# Sheet1.net
KiCad netlist of a schematic drawn in Altium Designer
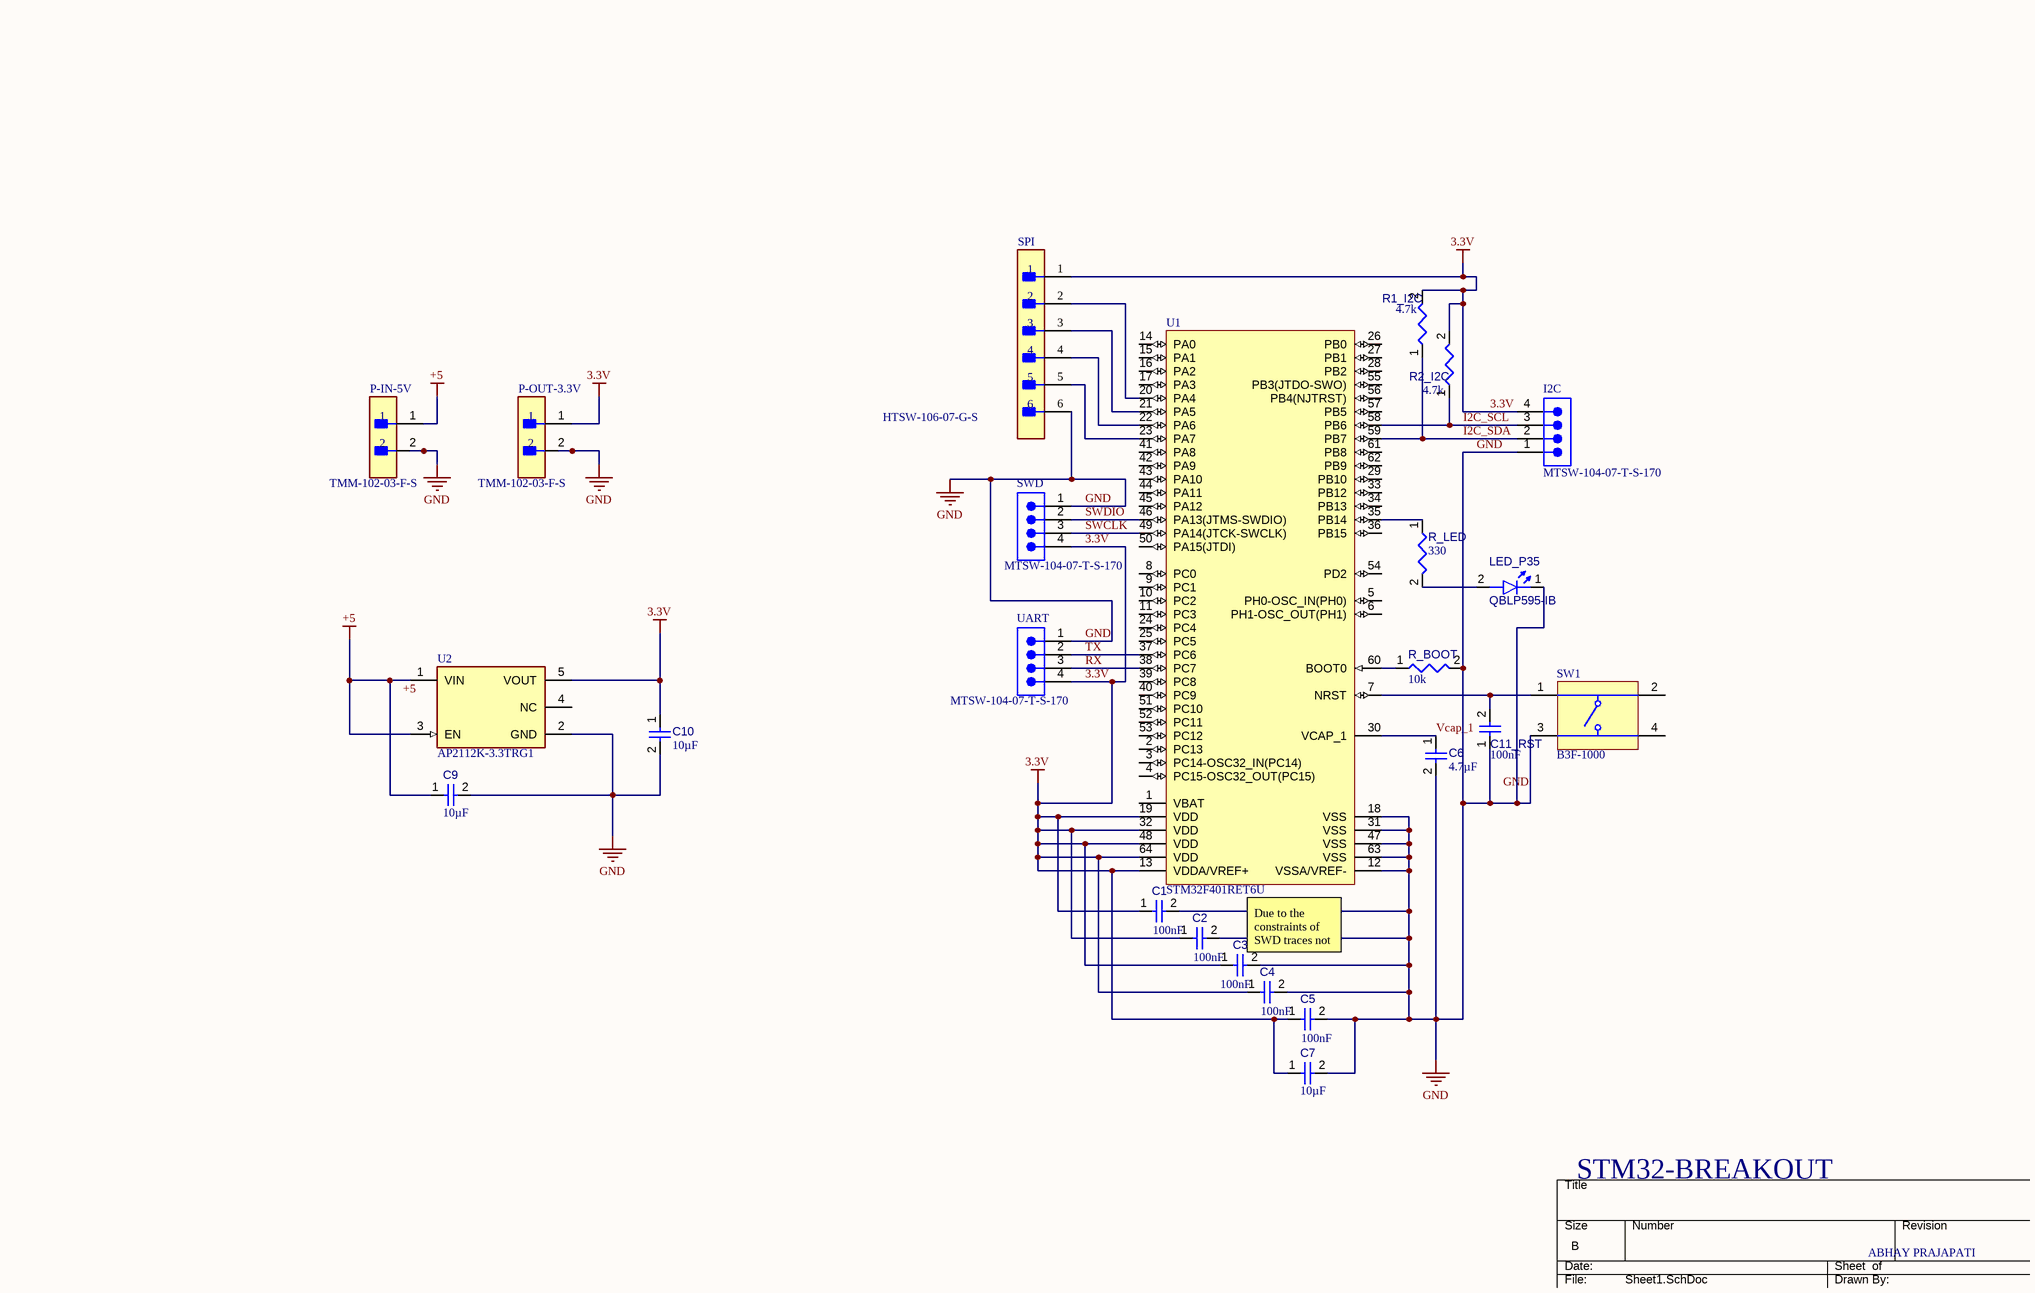
[diagram p0: Sheet1.SchDoc]

(export (version "E")
  (design (tool "Eeschema 10.0.6"))
  (components
    (comp (ref "C1")
      (value "100nF")
      (footprint "CAPC0402(1005)60_L")
      (description "Chip Capacitor, 100nF +/-20%, 25V, 0402, Thickness 0.6 mm")
      (fields (field (name "TOLERANCE") "10%") (field (name "Comment") "Capacitor 100nF +/-20% 25V 0402"))
      (libsource (lib "Abhay Prajapati") (part "CAP-NP-2"))
    )
    (comp (ref "C2")
      (value "100nF")
      (footprint "CAPC0402(1005)60_L")
      (description "Chip Capacitor, 100nF +/-20%, 25V, 0402, Thickness 0.6 mm")
      (fields (field (name "TOLERANCE") "10%") (field (name "Comment") "Capacitor 100nF +/-20% 25V 0402"))
      (libsource (lib "Abhay Prajapati") (part "CAP-NP-2"))
    )
    (comp (ref "C3_NOT")
      (value "100nF")
      (footprint "CAPC0402(1005)60_L")
      (description "Chip Capacitor, 100nF +/-20%, 25V, 0402, Thickness 0.6 mm")
      (fields (field (name "TOLERANCE") "10%") (field (name "Comment") "Capacitor 100nF +/-20% 25V 0402"))
      (libsource (lib "Abhay Prajapati") (part "CAP-NP-2"))
    )
    (comp (ref "C4")
      (value "100nF")
      (footprint "CAPC0402(1005)60_L")
      (description "Chip Capacitor, 100nF +/-20%, 25V, 0402, Thickness 0.6 mm")
      (fields (field (name "TOLERANCE") "10%") (field (name "Comment") "Capacitor 100nF +/-20% 25V 0402"))
      (libsource (lib "Abhay Prajapati") (part "CAP-NP-2"))
    )
    (comp (ref "C5")
      (value "100nF")
      (footprint "CAPC0402(1005)60_L")
      (description "Chip Capacitor, 100nF +/-20%, 25V, 0402, Thickness 0.6 mm")
      (fields (field (name "TOLERANCE") "10%") (field (name "Comment") "Capacitor 100nF +/-20% 25V 0402"))
      (libsource (lib "Abhay Prajapati") (part "CAP-NP-2"))
    )
    (comp (ref "C6")
      (value "4.7µF")
      (footprint "CAPC0603(1608)100_L")
      (description "Chip Capacitor, 4.7µF +/-20%, 10V, 0603, Thickness 1 mm")
      (fields (field (name "TOLERANCE") "10%") (field (name "Comment") "Capacitor 4.7µF +/-20% 10V 0603"))
      (libsource (lib "Abhay Prajapati") (part "CAP-NP-2"))
    )
    (comp (ref "C7")
      (value "10µF")
      (footprint "FP-GRM21B-0_1-IPC_B")
      (description "16V 10uF X5R ±10% 0805 Multilayer Ceramic Capacitors MLCC - SMD/SMT ROHS")
      (fields (field (name "TOLERANCE") "10%") (field (name "Comment") "GRM21BR61C106KE15K"))
      (libsource (lib "Abhay Prajapati") (part "CAP-NP-2"))
    )
    (comp (ref "C9")
      (value "10µF")
      (footprint "CAPC2013X135X45NL10T25")
      (description "Chip Capacitor, 10 uF, +/- 10%, 16 V, 0805 (2012 Metric)")
      (fields (field (name "TOLERANCE") "10%") (field (name "Comment") "Capacitor 10 uF +/- 10% 16 V 0805"))
      (libsource (lib "Abhay Prajapati") (part "CAP-NP-2"))
    )
    (comp (ref "C10")
      (value "10µF")
      (footprint "CAPC2013X135X45NL10T25")
      (description "Chip Capacitor, 10 uF, +/- 10%, 16 V, 0805 (2012 Metric)")
      (fields (field (name "TOLERANCE") "10%") (field (name "Comment") "Capacitor 10 uF +/- 10% 16 V 0805"))
      (libsource (lib "Abhay Prajapati") (part "CAP-NP-2"))
    )
    (comp (ref "C11_RST")
      (value "100nF")
      (footprint "CAPC1608X90X40NL10T20")
      (description "Chip Capacitor, 100 nF, +/- 10%, 50 V, 0603 (1608 Metric)")
      (fields (field (name "TOLERANCE") "10%") (field (name "Comment") "Capacitor 100 nF +/-10% 50 V 0603"))
      (libsource (lib "Abhay Prajapati") (part "CAP-NP-2"))
    )
    (comp (ref "I2C")
      (value "MTSW-104-07-T-S-170")
      (footprint "SMTC-MTSW-104-07-X-S-170")
      (description "Headers & Wire Housings Variable Height PCB Header Strips, 0.100 pitch")
      (libsource (lib "Abhay Prajapati") (part "SMTC-MTSW-104-07-X-S-170"))
    )
    (comp (ref "LED_P35")
      (value "QBLP595-IB")
      (footprint "QTB-QBLP595_V")
      (description "Chip LED 0402, Blue, 0.02 A, 3.1 to 3.7 V, -40 to 80 degC, 2-Pin SMD, RoHS, Tape and Reel")
      (libsource (lib "Abhay Prajapati") (part "LED-KA-2"))
    )
    (comp (ref "P-IN-5V")
      (value "TMM-102-03-F-S")
      (footprint "FP-TMM-102-03-F-S-MFG")
      (description "Pin Header, Board-to-Board, Wire-to-Board, 2 mm, 1 Rows, 2 Contacts, Through Hole, TMM")
      (libsource (lib "Abhay Prajapati") (part "3bc925449376181038e59eaffc5286c"))
    )
    (comp (ref "P-OUT-3.3V")
      (value "TMM-102-03-F-S")
      (footprint "FP-TMM-102-03-F-S-MFG")
      (description "Pin Header, Board-to-Board, Wire-to-Board, 2 mm, 1 Rows, 2 Contacts, Through Hole, TMM")
      (libsource (lib "Abhay Prajapati") (part "3bc925449376181038e59eaffc5286c"))
    )
    (comp (ref "R1_I2C")
      (value "4.7k")
      (footprint "RESC0402(1005)_L")
      (description "4K7 0.063W 1% 0402 (1005 Metric)  SMD")
      (fields (field (name "TOLERANCE") "1%") (field (name "POWER") "63mW"))
      (libsource (lib "Abhay Prajapati") (part "4D7KR2F"))
    )
    (comp (ref "R2_I2C")
      (value "4.7k")
      (footprint "RESC0402(1005)_L")
      (description "4K7 0.063W 1% 0402 (1005 Metric)  SMD")
      (fields (field (name "TOLERANCE") "1%") (field (name "POWER") "63mW"))
      (libsource (lib "Abhay Prajapati") (part "4D7KR2F"))
    )
    (comp (ref "R_BOOT")
      (value "10k")
      (footprint "RESC3216X60X45ML15T20")
      (description "Chip Resistor, 10 KOhm, +/- 1%, 0.25 W, -55 to 155 degC, 1206 (3216 Metric)")
      (fields (field (name "TOLERANCE") "1%") (field (name "POWER") "250mW"))
      (libsource (lib "Abhay Prajapati") (part "RES-2"))
    )
    (comp (ref "R_LED")
      (value "330")
      (footprint "RESC0402(1005)_L")
      (description "330R 0.063W 5% 0402 (1005 Metric)  SMD")
      (fields (field (name "TOLERANCE") "5%") (field (name "POWER") "63mW"))
      (libsource (lib "Abhay Prajapati") (part "330R2J"))
    )
    (comp (ref "SPI")
      (value "HTSW-106-07-G-S")
      (footprint "FP-HTSW-106-07-G-S-MFG")
      (description "Pin Header, Vertical, Board-to-Board, 2.54 mm, 1 Rows, 6 Contacts, Through Hole, HTSW Series")
      (libsource (lib "Abhay Prajapati") (part "f2cb566baf1c37ab5a3b8e90bbeafd6"))
    )
    (comp (ref "SW1")
      (value "B3F-1000")
      (footprint "OMRON-B3F-1000-4_V")
      (description "Tactile Switch, SPST-NO, 0.05 A, 24 V, -25 to 70 degC, 4-Pin THD, RoHS, Bulk")
      (fields (field (name "MANUFACTURER") "Omron Electronic Components"))
      (libsource (lib "Abhay Prajapati") (part "SW-SPST-4_A"))
    )
    (comp (ref "SWD")
      (value "MTSW-104-07-T-S-170")
      (footprint "SMTC-MTSW-104-07-X-S-170")
      (description "Headers & Wire Housings Variable Height PCB Header Strips, 0.100 pitch")
      (libsource (lib "Abhay Prajapati") (part "SMTC-MTSW-104-07-X-S-170"))
    )
    (comp (ref "U1")
      (value "STM32F401RET6U")
      (footprint "STM-LQFP64_L")
      (description "MCU 32-Bit STM32 ARM Cortex M4 RISC 512KB Flash 2.5V/3.3V 64-Pin LQFP Tray")
      (libsource (lib "Abhay Prajapati") (part "MC-ARM-STM32F401-LQFP64"))
    )
    (comp (ref "U2")
      (value "AP2112K-3.3TRG1")
      (footprint "FP-SOT25-IPC_B")
      (description "AP2112 Series 0.6 A 3.3 V Fixed Output SMT LDO Linear Regulator - SOT23-5")
      (libsource (lib "Abhay Prajapati") (part "c8ab751aee5229183125ab046a11caa"))
    )
    (comp (ref "UART")
      (value "MTSW-104-07-T-S-170")
      (footprint "SMTC-MTSW-104-07-X-S-170")
      (description "Headers & Wire Housings Variable Height PCB Header Strips, 0.100 pitch")
      (libsource (lib "Abhay Prajapati") (part "SMTC-MTSW-104-07-X-S-170"))
    )
  )
  (nets
    (net (code "1") (name "+5") (class "Default")
      (node (ref "C9") (pin "1") (pinfunction "1_1") (pintype "passive"))
      (node (ref "P-IN-5V") (pin "1") (pinfunction "1_1") (pintype "passive"))
      (node (ref "U2") (pin "1") (pinfunction "VIN_1") (pintype "power_in"))
      (node (ref "U2") (pin "3") (pinfunction "EN_3") (pintype "input"))
    )
    (net (code "2") (name "/I2C_SCL") (class "Default")
      (node (ref "I2C") (pin "3") (pinfunction "3_3") (pintype "passive"))
      (node (ref "R2_I2C") (pin "1") (pinfunction "1_1") (pintype "passive"))
      (node (ref "U1") (pin "58") (pinfunction "PB6_58") (pintype "bidirectional"))
    )
    (net (code "3") (name "/I2C_SDA") (class "Default")
      (node (ref "I2C") (pin "2") (pinfunction "2_2") (pintype "passive"))
      (node (ref "R1_I2C") (pin "1") (pinfunction "1_1") (pintype "passive"))
      (node (ref "U1") (pin "59") (pinfunction "PB7_59") (pintype "bidirectional"))
    )
    (net (code "4") (name "/RX") (class "Default")
      (node (ref "U1") (pin "38") (pinfunction "PC7_38") (pintype "bidirectional"))
      (node (ref "UART") (pin "3") (pinfunction "3_3") (pintype "passive"))
    )
    (net (code "5") (name "/SWCLK") (class "Default")
      (node (ref "SWD") (pin "3") (pinfunction "3_3") (pintype "passive"))
      (node (ref "U1") (pin "49") (pinfunction "PA14(JTCK-SWCLK)_49") (pintype "bidirectional"))
    )
    (net (code "6") (name "/SWDIO") (class "Default")
      (node (ref "SWD") (pin "2") (pinfunction "2_2") (pintype "passive"))
      (node (ref "U1") (pin "46") (pinfunction "PA13(JTMS-SWDIO)_46") (pintype "bidirectional"))
    )
    (net (code "7") (name "/TX") (class "Default")
      (node (ref "U1") (pin "37") (pinfunction "PC6_37") (pintype "bidirectional"))
      (node (ref "UART") (pin "2") (pinfunction "2_2") (pintype "passive"))
    )
    (net (code "8") (name "/Vcap_1") (class "Default")
      (node (ref "C6") (pin "1") (pinfunction "1_1") (pintype "passive"))
      (node (ref "U1") (pin "30") (pinfunction "VCAP_1_30") (pintype "passive"))
    )
    (net (code "9") (name "3.3V") (class "Default")
      (node (ref "C1") (pin "1") (pinfunction "1_1") (pintype "passive"))
      (node (ref "C10") (pin "1") (pinfunction "1_1") (pintype "passive"))
      (node (ref "C2") (pin "1") (pinfunction "1_1") (pintype "passive"))
      (node (ref "C3_NOT") (pin "1") (pinfunction "1_1") (pintype "passive"))
      (node (ref "C4") (pin "1") (pinfunction "1_1") (pintype "passive"))
      (node (ref "C5") (pin "1") (pinfunction "1_1") (pintype "passive"))
      (node (ref "C7") (pin "1") (pinfunction "1_1") (pintype "passive"))
      (node (ref "I2C") (pin "4") (pinfunction "4_4") (pintype "passive"))
      (node (ref "P-OUT-3.3V") (pin "1") (pinfunction "1_1") (pintype "passive"))
      (node (ref "R1_I2C") (pin "2") (pinfunction "2_2") (pintype "passive"))
      (node (ref "R2_I2C") (pin "2") (pinfunction "2_2") (pintype "passive"))
      (node (ref "SPI") (pin "1") (pinfunction "1_1") (pintype "passive"))
      (node (ref "SWD") (pin "4") (pinfunction "4_4") (pintype "passive"))
      (node (ref "U1") (pin "13") (pinfunction "VDDA/VREF+_13") (pintype "power_in"))
      (node (ref "U1") (pin "19") (pinfunction "VDD_19") (pintype "power_in"))
      (node (ref "U1") (pin "32") (pinfunction "VDD_32") (pintype "power_in"))
      (node (ref "U1") (pin "48") (pinfunction "VDD_48") (pintype "power_in"))
      (node (ref "U1") (pin "64") (pinfunction "VDD_64") (pintype "power_in"))
      (node (ref "U2") (pin "5") (pinfunction "VOUT_5") (pintype "power_in"))
      (node (ref "UART") (pin "4") (pinfunction "4_4") (pintype "passive"))
    )
    (net (code "10") (name "GND") (class "Default")
      (node (ref "C1") (pin "2") (pinfunction "2_2") (pintype "passive"))
      (node (ref "C10") (pin "2") (pinfunction "2_2") (pintype "passive"))
      (node (ref "C11_RST") (pin "1") (pinfunction "1_1") (pintype "passive"))
      (node (ref "C2") (pin "2") (pinfunction "2_2") (pintype "passive"))
      (node (ref "C3_NOT") (pin "2") (pinfunction "2_2") (pintype "passive"))
      (node (ref "C4") (pin "2") (pinfunction "2_2") (pintype "passive"))
      (node (ref "C5") (pin "2") (pinfunction "2_2") (pintype "passive"))
      (node (ref "C6") (pin "2") (pinfunction "2_2") (pintype "passive"))
      (node (ref "C7") (pin "2") (pinfunction "2_2") (pintype "passive"))
      (node (ref "C9") (pin "2") (pinfunction "2_2") (pintype "passive"))
      (node (ref "I2C") (pin "1") (pinfunction "1_1") (pintype "passive"))
      (node (ref "LED_P35") (pin "1") (pinfunction "K_1") (pintype "passive"))
      (node (ref "P-IN-5V") (pin "2") (pinfunction "2_2") (pintype "passive"))
      (node (ref "P-OUT-3.3V") (pin "2") (pinfunction "2_2") (pintype "passive"))
      (node (ref "R_BOOT") (pin "2") (pinfunction "2_2") (pintype "passive"))
      (node (ref "SPI") (pin "6") (pinfunction "6_6") (pintype "passive"))
      (node (ref "SW1") (pin "3") (pinfunction "3_3") (pintype "passive"))
      (node (ref "SWD") (pin "1") (pinfunction "1_1") (pintype "passive"))
      (node (ref "U1") (pin "12") (pinfunction "VSSA/VREF-_12") (pintype "power_in"))
      (node (ref "U1") (pin "18") (pinfunction "VSS_18") (pintype "power_in"))
      (node (ref "U1") (pin "31") (pinfunction "VSS_31") (pintype "power_in"))
      (node (ref "U1") (pin "47") (pinfunction "VSS_47") (pintype "power_in"))
      (node (ref "U1") (pin "63") (pinfunction "VSS_63") (pintype "power_in"))
      (node (ref "U2") (pin "2") (pinfunction "GND_2") (pintype "power_in"))
      (node (ref "UART") (pin "1") (pinfunction "1_1") (pintype "passive"))
    )
    (net (code "11") (name "Net-(LED_P35-A)") (class "Default")
      (node (ref "LED_P35") (pin "2") (pinfunction "A_2") (pintype "passive"))
      (node (ref "R_LED") (pin "2") (pinfunction "2_2") (pintype "passive"))
    )
    (net (code "12") (name "Net-(U1-BOOT0)") (class "Default")
      (node (ref "R_BOOT") (pin "1") (pinfunction "1_1") (pintype "passive"))
      (node (ref "U1") (pin "60") (pinfunction "BOOT0_60") (pintype "input"))
    )
    (net (code "13") (name "Net-(U1-NRST)") (class "Default")
      (node (ref "C11_RST") (pin "2") (pinfunction "2_2") (pintype "passive"))
      (node (ref "SW1") (pin "1") (pinfunction "1_1") (pintype "passive"))
      (node (ref "U1") (pin "7") (pinfunction "NRST_7") (pintype "bidirectional"))
    )
    (net (code "14") (name "Net-(U1-PA4)") (class "Default")
      (node (ref "SPI") (pin "2") (pinfunction "2_2") (pintype "passive"))
      (node (ref "U1") (pin "20") (pinfunction "PA4_20") (pintype "bidirectional"))
    )
    (net (code "15") (name "Net-(U1-PA5)") (class "Default")
      (node (ref "SPI") (pin "3") (pinfunction "3_3") (pintype "passive"))
      (node (ref "U1") (pin "21") (pinfunction "PA5_21") (pintype "bidirectional"))
    )
    (net (code "16") (name "Net-(U1-PA6)") (class "Default")
      (node (ref "SPI") (pin "4") (pinfunction "4_4") (pintype "passive"))
      (node (ref "U1") (pin "22") (pinfunction "PA6_22") (pintype "bidirectional"))
    )
    (net (code "17") (name "Net-(U1-PA7)") (class "Default")
      (node (ref "SPI") (pin "5") (pinfunction "5_5") (pintype "passive"))
      (node (ref "U1") (pin "23") (pinfunction "PA7_23") (pintype "bidirectional"))
    )
    (net (code "18") (name "Net-(U1-PB14)") (class "Default")
      (node (ref "R_LED") (pin "1") (pinfunction "1_1") (pintype "passive"))
      (node (ref "U1") (pin "35") (pinfunction "PB14_35") (pintype "bidirectional"))
    )
    (net (code "19") (name "unconnected-(SW1-Pad2)") (class "Default")
      (node (ref "SW1") (pin "2") (pinfunction "2_2") (pintype "passive"))
    )
    (net (code "20") (name "unconnected-(SW1-Pad4)") (class "Default")
      (node (ref "SW1") (pin "4") (pinfunction "4_4") (pintype "passive"))
    )
    (net (code "21") (name "unconnected-(U1-PA0-Pad14)") (class "Default")
      (node (ref "U1") (pin "14") (pinfunction "PA0_14") (pintype "bidirectional"))
    )
    (net (code "22") (name "unconnected-(U1-PA1-Pad15)") (class "Default")
      (node (ref "U1") (pin "15") (pinfunction "PA1_15") (pintype "bidirectional"))
    )
    (net (code "23") (name "unconnected-(U1-PA2-Pad16)") (class "Default")
      (node (ref "U1") (pin "16") (pinfunction "PA2_16") (pintype "bidirectional"))
    )
    (net (code "24") (name "unconnected-(U1-PA3-Pad17)") (class "Default")
      (node (ref "U1") (pin "17") (pinfunction "PA3_17") (pintype "bidirectional"))
    )
    (net (code "25") (name "unconnected-(U1-PA8-Pad41)") (class "Default")
      (node (ref "U1") (pin "41") (pinfunction "PA8_41") (pintype "bidirectional"))
    )
    (net (code "26") (name "unconnected-(U1-PA9-Pad42)") (class "Default")
      (node (ref "U1") (pin "42") (pinfunction "PA9_42") (pintype "bidirectional"))
    )
    (net (code "27") (name "unconnected-(U1-PA10-Pad43)") (class "Default")
      (node (ref "U1") (pin "43") (pinfunction "PA10_43") (pintype "bidirectional"))
    )
    (net (code "28") (name "unconnected-(U1-PA11-Pad44)") (class "Default")
      (node (ref "U1") (pin "44") (pinfunction "PA11_44") (pintype "bidirectional"))
    )
    (net (code "29") (name "unconnected-(U1-PA12-Pad45)") (class "Default")
      (node (ref "U1") (pin "45") (pinfunction "PA12_45") (pintype "bidirectional"))
    )
    (net (code "30") (name "unconnected-(U1-PA15(JTDI)-Pad50)") (class "Default")
      (node (ref "U1") (pin "50") (pinfunction "PA15(JTDI)_50") (pintype "bidirectional"))
    )
    (net (code "31") (name "unconnected-(U1-PB0-Pad26)") (class "Default")
      (node (ref "U1") (pin "26") (pinfunction "PB0_26") (pintype "bidirectional"))
    )
    (net (code "32") (name "unconnected-(U1-PB1-Pad27)") (class "Default")
      (node (ref "U1") (pin "27") (pinfunction "PB1_27") (pintype "bidirectional"))
    )
    (net (code "33") (name "unconnected-(U1-PB2-Pad28)") (class "Default")
      (node (ref "U1") (pin "28") (pinfunction "PB2_28") (pintype "bidirectional"))
    )
    (net (code "34") (name "unconnected-(U1-PB3(JTDO-SWO)-Pad55)") (class "Default")
      (node (ref "U1") (pin "55") (pinfunction "PB3(JTDO-SWO)_55") (pintype "bidirectional"))
    )
    (net (code "35") (name "unconnected-(U1-PB4(NJTRST)-Pad56)") (class "Default")
      (node (ref "U1") (pin "56") (pinfunction "PB4(NJTRST)_56") (pintype "bidirectional"))
    )
    (net (code "36") (name "unconnected-(U1-PB5-Pad57)") (class "Default")
      (node (ref "U1") (pin "57") (pinfunction "PB5_57") (pintype "bidirectional"))
    )
    (net (code "37") (name "unconnected-(U1-PB8-Pad61)") (class "Default")
      (node (ref "U1") (pin "61") (pinfunction "PB8_61") (pintype "bidirectional"))
    )
    (net (code "38") (name "unconnected-(U1-PB9-Pad62)") (class "Default")
      (node (ref "U1") (pin "62") (pinfunction "PB9_62") (pintype "bidirectional"))
    )
    (net (code "39") (name "unconnected-(U1-PB10-Pad29)") (class "Default")
      (node (ref "U1") (pin "29") (pinfunction "PB10_29") (pintype "bidirectional"))
    )
    (net (code "40") (name "unconnected-(U1-PB12-Pad33)") (class "Default")
      (node (ref "U1") (pin "33") (pinfunction "PB12_33") (pintype "bidirectional"))
    )
    (net (code "41") (name "unconnected-(U1-PB13-Pad34)") (class "Default")
      (node (ref "U1") (pin "34") (pinfunction "PB13_34") (pintype "bidirectional"))
    )
    (net (code "42") (name "unconnected-(U1-PB15-Pad36)") (class "Default")
      (node (ref "U1") (pin "36") (pinfunction "PB15_36") (pintype "bidirectional"))
    )
    (net (code "43") (name "unconnected-(U1-PC0-Pad8)") (class "Default")
      (node (ref "U1") (pin "8") (pinfunction "PC0_8") (pintype "bidirectional"))
    )
    (net (code "44") (name "unconnected-(U1-PC1-Pad9)") (class "Default")
      (node (ref "U1") (pin "9") (pinfunction "PC1_9") (pintype "bidirectional"))
    )
    (net (code "45") (name "unconnected-(U1-PC2-Pad10)") (class "Default")
      (node (ref "U1") (pin "10") (pinfunction "PC2_10") (pintype "bidirectional"))
    )
    (net (code "46") (name "unconnected-(U1-PC3-Pad11)") (class "Default")
      (node (ref "U1") (pin "11") (pinfunction "PC3_11") (pintype "bidirectional"))
    )
    (net (code "47") (name "unconnected-(U1-PC4-Pad24)") (class "Default")
      (node (ref "U1") (pin "24") (pinfunction "PC4_24") (pintype "bidirectional"))
    )
    (net (code "48") (name "unconnected-(U1-PC5-Pad25)") (class "Default")
      (node (ref "U1") (pin "25") (pinfunction "PC5_25") (pintype "bidirectional"))
    )
    (net (code "49") (name "unconnected-(U1-PC8-Pad39)") (class "Default")
      (node (ref "U1") (pin "39") (pinfunction "PC8_39") (pintype "bidirectional"))
    )
    (net (code "50") (name "unconnected-(U1-PC9-Pad40)") (class "Default")
      (node (ref "U1") (pin "40") (pinfunction "PC9_40") (pintype "bidirectional"))
    )
    (net (code "51") (name "unconnected-(U1-PC10-Pad51)") (class "Default")
      (node (ref "U1") (pin "51") (pinfunction "PC10_51") (pintype "bidirectional"))
    )
    (net (code "52") (name "unconnected-(U1-PC11-Pad52)") (class "Default")
      (node (ref "U1") (pin "52") (pinfunction "PC11_52") (pintype "bidirectional"))
    )
    (net (code "53") (name "unconnected-(U1-PC12-Pad53)") (class "Default")
      (node (ref "U1") (pin "53") (pinfunction "PC12_53") (pintype "bidirectional"))
    )
    (net (code "54") (name "unconnected-(U1-PC13-Pad2)") (class "Default")
      (node (ref "U1") (pin "2") (pinfunction "PC13_2") (pintype "bidirectional"))
    )
    (net (code "55") (name "unconnected-(U1-PC14-OSC32_IN(PC14)-Pad3)") (class "Default")
      (node (ref "U1") (pin "3") (pinfunction "PC14-OSC32_IN(PC14)_3") (pintype "bidirectional"))
    )
    (net (code "56") (name "unconnected-(U1-PC15-OSC32_OUT(PC15)-Pad4)") (class "Default")
      (node (ref "U1") (pin "4") (pinfunction "PC15-OSC32_OUT(PC15)_4") (pintype "bidirectional"))
    )
    (net (code "57") (name "unconnected-(U1-PD2-Pad54)") (class "Default")
      (node (ref "U1") (pin "54") (pinfunction "PD2_54") (pintype "bidirectional"))
    )
    (net (code "58") (name "unconnected-(U1-PH0-OSC_IN(PH0)-Pad5)") (class "Default")
      (node (ref "U1") (pin "5") (pinfunction "PH0-OSC_IN(PH0)_5") (pintype "bidirectional"))
    )
    (net (code "59") (name "unconnected-(U1-PH1-OSC_OUT(PH1)-Pad6)") (class "Default")
      (node (ref "U1") (pin "6") (pinfunction "PH1-OSC_OUT(PH1)_6") (pintype "bidirectional"))
    )
    (net (code "60") (name "unconnected-(U1-VBAT-Pad1)") (class "Default")
      (node (ref "U1") (pin "1") (pinfunction "VBAT_1") (pintype "power_in"))
    )
    (net (code "61") (name "unconnected-(U2-NC-Pad4)") (class "Default")
      (node (ref "U2") (pin "4") (pinfunction "NC_4") (pintype "passive"))
    )
  )
)
